# Adapter.net
KiCad netlist of a schematic drawn in EAGLE
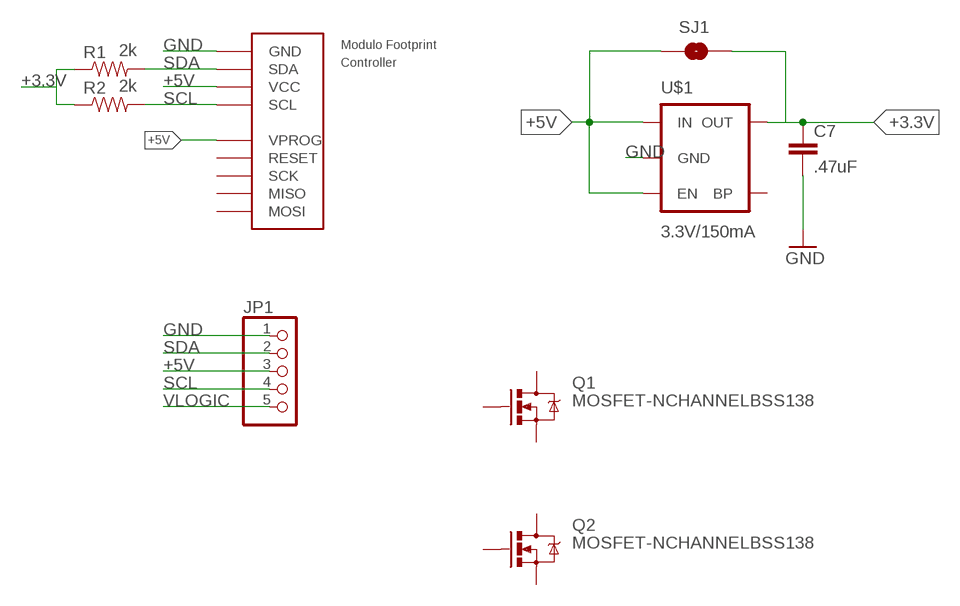
[diagram p0: schematic, sheet 1]

(export (version "E")
  (design (tool "Eeschema 10.0.6"))
  (components
    (comp (ref "C7")
      (value ".47uF")
      (footprint "eagle-import:0805")
      (libsource (lib "eagle-import") (part "CAP0805"))
    )
    (comp (ref "FOOTPRINT")
      (value "Controller")
      (footprint "eagle-import:FOOTPRINT2")
      (fields (field (name "BOARD") "Controller") (field (name "VERSION") "v4"))
      (libsource (lib "eagle-import") (part "FOOTPRINTFOOTPRINT-2"))
    )
    (comp (ref "JP1")
      (value "PINHD-1X5/90")
      (footprint "eagle-import:1X05_90")
      (libsource (lib "eagle-import") (part "PINHD-1X5/90"))
    )
    (comp (ref "Q1")
      (value "MOSFET-NCHANNELBSS138")
      (footprint "eagle-import:SOT23")
      (libsource (lib "eagle-import") (part "MOSFET-NCHANNELBSS138"))
    )
    (comp (ref "Q2")
      (value "MOSFET-NCHANNELBSS138")
      (footprint "eagle-import:SOT23")
      (libsource (lib "eagle-import") (part "MOSFET-NCHANNELBSS138"))
    )
    (comp (ref "R1")
      (value "2k")
      (footprint "eagle-import:0805")
      (libsource (lib "eagle-import") (part "RESISTOR0805-RES"))
    )
    (comp (ref "R2")
      (value "2k")
      (footprint "eagle-import:0805")
      (libsource (lib "eagle-import") (part "RESISTOR0805-RES"))
    )
    (comp (ref "SJ1")
      (value "SOLDERJUMPERNO")
      (footprint "eagle-import:SJ_2S-NO")
      (libsource (lib "eagle-import") (part "SOLDERJUMPERNO"))
    )
    (comp (ref "U$1")
      (value "3.3V/150mA")
      (footprint "eagle-import:SOT23-5")
      (libsource (lib "eagle-import") (part "V_REG_MIC52053.3V"))
    )
  )
  (nets
    (net (code "1") (name "+3.3V") (class "Default")
      (node (ref "C7") (pin "1") (pinfunction "1_1") (pintype "passive"))
      (node (ref "R1") (pin "1") (pinfunction "1_1") (pintype "passive"))
      (node (ref "R2") (pin "1") (pinfunction "1_1") (pintype "passive"))
      (node (ref "SJ1") (pin "2") (pinfunction "2_2") (pintype "passive"))
      (node (ref "U$1") (pin "5") (pinfunction "OUT_5") (pintype "passive"))
    )
    (net (code "2") (name "+5V") (class "Default")
      (node (ref "FOOTPRINT") (pin "BUS2") (pinfunction "VCC_BUS2") (pintype "bidirectional"))
      (node (ref "FOOTPRINT") (pin "PROG0") (pinfunction "VPROG_PROG0") (pintype "bidirectional"))
      (node (ref "JP1") (pin "3") (pinfunction "3_3") (pintype "passive"))
      (node (ref "SJ1") (pin "1") (pinfunction "1_1") (pintype "passive"))
      (node (ref "U$1") (pin "1") (pinfunction "IN_1") (pintype "input"))
      (node (ref "U$1") (pin "3") (pinfunction "EN_3") (pintype "input"))
    )
    (net (code "3") (name "/SCL") (class "Default")
      (node (ref "FOOTPRINT") (pin "BUS3") (pinfunction "SCL_BUS3") (pintype "bidirectional"))
      (node (ref "JP1") (pin "4") (pinfunction "4_4") (pintype "passive"))
      (node (ref "R2") (pin "2") (pinfunction "2_2") (pintype "passive"))
    )
    (net (code "4") (name "/SDA") (class "Default")
      (node (ref "FOOTPRINT") (pin "BUS1") (pinfunction "SDA_BUS1") (pintype "bidirectional"))
      (node (ref "JP1") (pin "2") (pinfunction "2_2") (pintype "passive"))
      (node (ref "R1") (pin "2") (pinfunction "2_2") (pintype "passive"))
    )
    (net (code "5") (name "/VLOGIC") (class "Default")
      (node (ref "JP1") (pin "5") (pinfunction "5_5") (pintype "passive"))
    )
    (net (code "6") (name "GND") (class "Default")
      (node (ref "C7") (pin "2") (pinfunction "2_2") (pintype "passive"))
      (node (ref "FOOTPRINT") (pin "BUS0") (pinfunction "GND_BUS0") (pintype "bidirectional"))
      (node (ref "JP1") (pin "1") (pinfunction "1_1") (pintype "passive"))
      (node (ref "U$1") (pin "2") (pinfunction "GND_2") (pintype "input"))
    )
    (net (code "7") (name "unconnected-(FOOTPRINT-MISO-PadPROG3)") (class "Default")
      (node (ref "FOOTPRINT") (pin "PROG3") (pinfunction "MISO_PROG3") (pintype "bidirectional"))
    )
    (net (code "8") (name "unconnected-(FOOTPRINT-MOSI-PadPROG4)") (class "Default")
      (node (ref "FOOTPRINT") (pin "PROG4") (pinfunction "MOSI_PROG4") (pintype "bidirectional"))
    )
    (net (code "9") (name "unconnected-(FOOTPRINT-RESET-PadPROG1)") (class "Default")
      (node (ref "FOOTPRINT") (pin "PROG1") (pinfunction "RESET_PROG1") (pintype "bidirectional"))
    )
    (net (code "10") (name "unconnected-(FOOTPRINT-SCK-PadPROG2)") (class "Default")
      (node (ref "FOOTPRINT") (pin "PROG2") (pinfunction "SCK_PROG2") (pintype "bidirectional"))
    )
    (net (code "11") (name "unconnected-(Q1-D-Pad3)") (class "Default")
      (node (ref "Q1") (pin "3") (pinfunction "D_3") (pintype "passive"))
    )
    (net (code "12") (name "unconnected-(Q1-G-Pad1)") (class "Default")
      (node (ref "Q1") (pin "1") (pinfunction "G_1") (pintype "passive"))
    )
    (net (code "13") (name "unconnected-(Q1-S-Pad2)") (class "Default")
      (node (ref "Q1") (pin "2") (pinfunction "S_2") (pintype "passive"))
    )
    (net (code "14") (name "unconnected-(Q2-D-Pad3)") (class "Default")
      (node (ref "Q2") (pin "3") (pinfunction "D_3") (pintype "passive"))
    )
    (net (code "15") (name "unconnected-(Q2-G-Pad1)") (class "Default")
      (node (ref "Q2") (pin "1") (pinfunction "G_1") (pintype "passive"))
    )
    (net (code "16") (name "unconnected-(Q2-S-Pad2)") (class "Default")
      (node (ref "Q2") (pin "2") (pinfunction "S_2") (pintype "passive"))
    )
    (net (code "17") (name "unconnected-(U$1-BP-Pad4)") (class "Default")
      (node (ref "U$1") (pin "4") (pinfunction "BP_4") (pintype "input"))
    )
  )
)
